# pca9544a_pcb.net
KiCad netlist of a schematic drawn in EAGLE
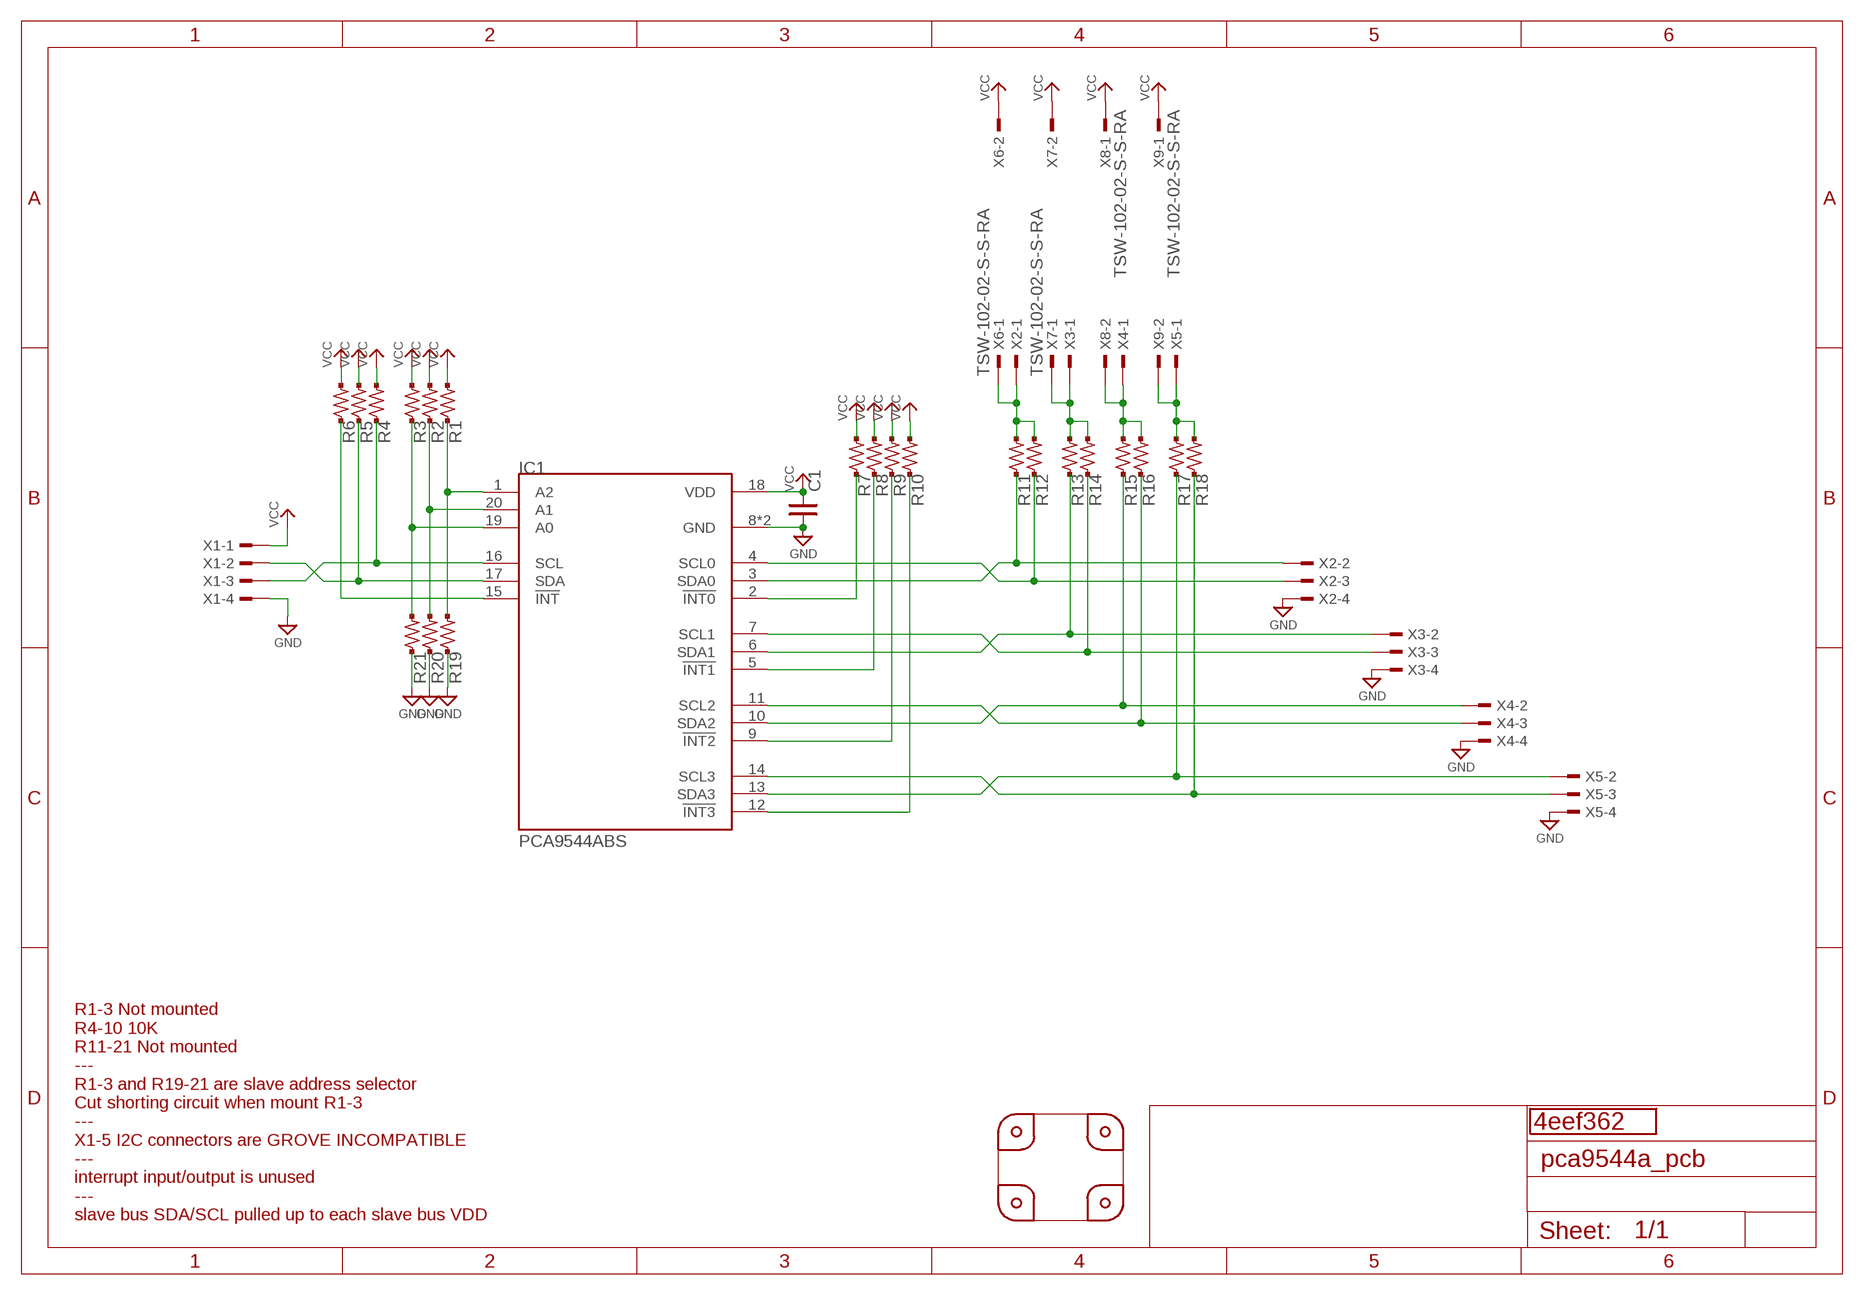
[diagram p0: schematic, sheet 1]

(export (version "E")
  (design (tool "Eeschema 10.0.6"))
  (components
    (comp (ref "C1")
      (value "C-SMD-0.1U-1608")
      (footprint "eagle-import:CR-1608")
      (libsource (lib "eagle-import") (part "C-SMD--16080.1U"))
    )
    (comp (ref "GIT1")
      (value "4eef362")
      (footprint "eagle-import:GIT-REVISION_1.2")
      (libsource (lib "eagle-import") (part "GIT-REVISION_1.2"))
    )
    (comp (ref "IC1")
      (value "PCA9544ABS")
      (footprint "eagle-import:QFN20-0.65P5.0X5.0")
      (libsource (lib "eagle-import") (part "PCA9544ABS"))
    )
    (comp (ref "P1")
      (value "PCB-CORNER")
      (footprint "eagle-import:PCB-CORNER")
      (libsource (lib "eagle-import") (part "PCB-CORNER"))
    )
    (comp (ref "P2")
      (value "PCB-CORNER")
      (footprint "eagle-import:PCB-CORNER")
      (libsource (lib "eagle-import") (part "PCB-CORNER"))
    )
    (comp (ref "P3")
      (value "PCB-CORNER")
      (footprint "eagle-import:PCB-CORNER")
      (libsource (lib "eagle-import") (part "PCB-CORNER"))
    )
    (comp (ref "P4")
      (value "PCB-CORNER")
      (footprint "eagle-import:PCB-CORNER")
      (libsource (lib "eagle-import") (part "PCB-CORNER"))
    )
    (comp (ref "R1")
      (value "R-US-10K-1608")
      (footprint "eagle-import:R-1608-PADPAD")
      (libsource (lib "eagle-import") (part "R-US--160810K"))
    )
    (comp (ref "R2")
      (value "R-US-10K-1608")
      (footprint "eagle-import:R-1608-PADPAD")
      (libsource (lib "eagle-import") (part "R-US--160810K"))
    )
    (comp (ref "R3")
      (value "R-US-10K-1608")
      (footprint "eagle-import:R-1608-PADPAD")
      (libsource (lib "eagle-import") (part "R-US--160810K"))
    )
    (comp (ref "R4")
      (value "R-US-10K-1608")
      (footprint "eagle-import:R-1608-PADPAD")
      (libsource (lib "eagle-import") (part "R-US--160810K"))
    )
    (comp (ref "R5")
      (value "R-US-10K-1608")
      (footprint "eagle-import:R-1608-PADPAD")
      (libsource (lib "eagle-import") (part "R-US--160810K"))
    )
    (comp (ref "R6")
      (value "R-US-10K-1608")
      (footprint "eagle-import:R-1608-PADPAD")
      (libsource (lib "eagle-import") (part "R-US--160810K"))
    )
    (comp (ref "R7")
      (value "R-US-10K-1608")
      (footprint "eagle-import:R-1608-PADPAD")
      (libsource (lib "eagle-import") (part "R-US--160810K"))
    )
    (comp (ref "R8")
      (value "R-US-10K-1608")
      (footprint "eagle-import:R-1608-PADPAD")
      (libsource (lib "eagle-import") (part "R-US--160810K"))
    )
    (comp (ref "R9")
      (value "R-US-10K-1608")
      (footprint "eagle-import:R-1608-PADPAD")
      (libsource (lib "eagle-import") (part "R-US--160810K"))
    )
    (comp (ref "R10")
      (value "R-US-10K-1608")
      (footprint "eagle-import:R-1608-PADPAD")
      (libsource (lib "eagle-import") (part "R-US--160810K"))
    )
    (comp (ref "R11")
      (value "R-US-10K-1608")
      (footprint "eagle-import:R-1608-PADPAD")
      (libsource (lib "eagle-import") (part "R-US--160810K"))
    )
    (comp (ref "R12")
      (value "R-US-10K-1608")
      (footprint "eagle-import:R-1608-PADPAD")
      (libsource (lib "eagle-import") (part "R-US--160810K"))
    )
    (comp (ref "R13")
      (value "R-US-10K-1608")
      (footprint "eagle-import:R-1608-PADPAD")
      (libsource (lib "eagle-import") (part "R-US--160810K"))
    )
    (comp (ref "R14")
      (value "R-US-10K-1608")
      (footprint "eagle-import:R-1608-PADPAD")
      (libsource (lib "eagle-import") (part "R-US--160810K"))
    )
    (comp (ref "R15")
      (value "R-US-10K-1608")
      (footprint "eagle-import:R-1608-PADPAD")
      (libsource (lib "eagle-import") (part "R-US--160810K"))
    )
    (comp (ref "R16")
      (value "R-US-10K-1608")
      (footprint "eagle-import:R-1608-PADPAD")
      (libsource (lib "eagle-import") (part "R-US--160810K"))
    )
    (comp (ref "R17")
      (value "R-US-10K-1608")
      (footprint "eagle-import:R-1608-PADPAD")
      (libsource (lib "eagle-import") (part "R-US--160810K"))
    )
    (comp (ref "R18")
      (value "R-US-10K-1608")
      (footprint "eagle-import:R-1608-PADPAD")
      (libsource (lib "eagle-import") (part "R-US--160810K"))
    )
    (comp (ref "R19")
      (value "R-US--1005SHORT")
      (footprint "eagle-import:R0402SHORT")
      (libsource (lib "eagle-import") (part "R-US--1005SHORT"))
    )
    (comp (ref "R20")
      (value "R-US--1005SHORT")
      (footprint "eagle-import:R0402SHORT")
      (libsource (lib "eagle-import") (part "R-US--1005SHORT"))
    )
    (comp (ref "R21")
      (value "R-US--1005SHORT")
      (footprint "eagle-import:R0402SHORT")
      (libsource (lib "eagle-import") (part "R-US--1005SHORT"))
    )
    (comp (ref "X1")
      (value "S4B-XH-A")
      (footprint "eagle-import:S4B-XH-A(LF)(SN)")
      (libsource (lib "eagle-import") (part "S4B-XH-A"))
    )
    (comp (ref "X2")
      (value "S4B-XH-A")
      (footprint "eagle-import:S4B-XH-A(LF)(SN)")
      (libsource (lib "eagle-import") (part "S4B-XH-A"))
    )
    (comp (ref "X3")
      (value "S4B-XH-A")
      (footprint "eagle-import:S4B-XH-A(LF)(SN)")
      (libsource (lib "eagle-import") (part "S4B-XH-A"))
    )
    (comp (ref "X4")
      (value "S4B-XH-A")
      (footprint "eagle-import:S4B-XH-A(LF)(SN)")
      (libsource (lib "eagle-import") (part "S4B-XH-A"))
    )
    (comp (ref "X5")
      (value "S4B-XH-A")
      (footprint "eagle-import:S4B-XH-A(LF)(SN)")
      (libsource (lib "eagle-import") (part "S4B-XH-A"))
    )
    (comp (ref "X6")
      (value "TSW-102-02-S-S-RA")
      (footprint "eagle-import:TSW-102-02-S-S-RA")
      (libsource (lib "eagle-import") (part "TSW-102-02-S-S-RA"))
    )
    (comp (ref "X7")
      (value "TSW-102-02-S-S-RA")
      (footprint "eagle-import:TSW-102-02-S-S-RA")
      (libsource (lib "eagle-import") (part "TSW-102-02-S-S-RA"))
    )
    (comp (ref "X8")
      (value "TSW-102-02-S-S-RA")
      (footprint "eagle-import:TSW-102-02-S-S-RA")
      (libsource (lib "eagle-import") (part "TSW-102-02-S-S-RA"))
    )
    (comp (ref "X9")
      (value "TSW-102-02-S-S-RA")
      (footprint "eagle-import:TSW-102-02-S-S-RA")
      (libsource (lib "eagle-import") (part "TSW-102-02-S-S-RA"))
    )
  )
  (nets
    (net (code "1") (name "GND") (class "Default")
      (node (ref "C1") (pin "2") (pinfunction "2_2") (pintype "passive"))
      (node (ref "IC1") (pin "8") (pinfunction "GND_8") (pintype "bidirectional"))
      (node (ref "IC1") (pin "EP") (pinfunction "GND_EP") (pintype "bidirectional"))
      (node (ref "R19") (pin "1") (pinfunction "1_1") (pintype "passive"))
      (node (ref "R19") (pin "2") (pinfunction "1_2") (pintype "passive"))
      (node (ref "R20") (pin "1") (pinfunction "1_1") (pintype "passive"))
      (node (ref "R20") (pin "2") (pinfunction "1_2") (pintype "passive"))
      (node (ref "R21") (pin "1") (pinfunction "1_1") (pintype "passive"))
      (node (ref "R21") (pin "2") (pinfunction "1_2") (pintype "passive"))
      (node (ref "X1") (pin "4") (pinfunction "1_4") (pintype "passive"))
      (node (ref "X2") (pin "4") (pinfunction "1_4") (pintype "passive"))
      (node (ref "X3") (pin "4") (pinfunction "1_4") (pintype "passive"))
      (node (ref "X4") (pin "4") (pinfunction "1_4") (pintype "passive"))
      (node (ref "X5") (pin "4") (pinfunction "1_4") (pintype "passive"))
    )
    (net (code "2") (name "Net-(IC1-A0)") (class "Default")
      (node (ref "IC1") (pin "19") (pinfunction "A0_19") (pintype "bidirectional"))
      (node (ref "R21") (pin "3") (pinfunction "2_3") (pintype "passive"))
      (node (ref "R3") (pin "1") (pinfunction "1_1") (pintype "passive"))
    )
    (net (code "3") (name "Net-(IC1-A1)") (class "Default")
      (node (ref "IC1") (pin "20") (pinfunction "A1_20") (pintype "bidirectional"))
      (node (ref "R2") (pin "1") (pinfunction "1_1") (pintype "passive"))
      (node (ref "R20") (pin "3") (pinfunction "2_3") (pintype "passive"))
    )
    (net (code "4") (name "Net-(IC1-A2)") (class "Default")
      (node (ref "IC1") (pin "1") (pinfunction "A2_1") (pintype "bidirectional"))
      (node (ref "R1") (pin "1") (pinfunction "1_1") (pintype "passive"))
      (node (ref "R19") (pin "3") (pinfunction "2_3") (pintype "passive"))
    )
    (net (code "5") (name "Net-(IC1-SCL)") (class "Default")
      (node (ref "IC1") (pin "16") (pinfunction "SCL_16") (pintype "bidirectional"))
      (node (ref "R4") (pin "1") (pinfunction "1_1") (pintype "passive"))
      (node (ref "X1") (pin "3") (pinfunction "1_3") (pintype "passive"))
    )
    (net (code "6") (name "Net-(IC1-SCL0)") (class "Default")
      (node (ref "IC1") (pin "4") (pinfunction "SCL0_4") (pintype "bidirectional"))
      (node (ref "R12") (pin "1") (pinfunction "1_1") (pintype "passive"))
      (node (ref "X2") (pin "3") (pinfunction "1_3") (pintype "passive"))
    )
    (net (code "7") (name "Net-(IC1-SCL1)") (class "Default")
      (node (ref "IC1") (pin "7") (pinfunction "SCL1_7") (pintype "bidirectional"))
      (node (ref "R14") (pin "1") (pinfunction "1_1") (pintype "passive"))
      (node (ref "X3") (pin "3") (pinfunction "1_3") (pintype "passive"))
    )
    (net (code "8") (name "Net-(IC1-SCL2)") (class "Default")
      (node (ref "IC1") (pin "11") (pinfunction "SCL2_11") (pintype "bidirectional"))
      (node (ref "R16") (pin "1") (pinfunction "1_1") (pintype "passive"))
      (node (ref "X4") (pin "3") (pinfunction "1_3") (pintype "passive"))
    )
    (net (code "9") (name "Net-(IC1-SCL3)") (class "Default")
      (node (ref "IC1") (pin "14") (pinfunction "SCL3_14") (pintype "bidirectional"))
      (node (ref "R18") (pin "1") (pinfunction "1_1") (pintype "passive"))
      (node (ref "X5") (pin "3") (pinfunction "1_3") (pintype "passive"))
    )
    (net (code "10") (name "Net-(IC1-SDA)") (class "Default")
      (node (ref "IC1") (pin "17") (pinfunction "SDA_17") (pintype "bidirectional"))
      (node (ref "R5") (pin "1") (pinfunction "1_1") (pintype "passive"))
      (node (ref "X1") (pin "2") (pinfunction "1_2") (pintype "passive"))
    )
    (net (code "11") (name "Net-(IC1-SDA0)") (class "Default")
      (node (ref "IC1") (pin "3") (pinfunction "SDA0_3") (pintype "bidirectional"))
      (node (ref "R11") (pin "1") (pinfunction "1_1") (pintype "passive"))
      (node (ref "X2") (pin "2") (pinfunction "1_2") (pintype "passive"))
    )
    (net (code "12") (name "Net-(IC1-SDA1)") (class "Default")
      (node (ref "IC1") (pin "6") (pinfunction "SDA1_6") (pintype "bidirectional"))
      (node (ref "R13") (pin "1") (pinfunction "1_1") (pintype "passive"))
      (node (ref "X3") (pin "2") (pinfunction "1_2") (pintype "passive"))
    )
    (net (code "13") (name "Net-(IC1-SDA2)") (class "Default")
      (node (ref "IC1") (pin "10") (pinfunction "SDA2_10") (pintype "bidirectional"))
      (node (ref "R15") (pin "1") (pinfunction "1_1") (pintype "passive"))
      (node (ref "X4") (pin "2") (pinfunction "1_2") (pintype "passive"))
    )
    (net (code "14") (name "Net-(IC1-SDA3)") (class "Default")
      (node (ref "IC1") (pin "13") (pinfunction "SDA3_13") (pintype "bidirectional"))
      (node (ref "R17") (pin "1") (pinfunction "1_1") (pintype "passive"))
      (node (ref "X5") (pin "2") (pinfunction "1_2") (pintype "passive"))
    )
    (net (code "15") (name "Net-(IC1-~{INT0})") (class "Default")
      (node (ref "IC1") (pin "2") (pinfunction "~{INT0}_2") (pintype "bidirectional"))
      (node (ref "R7") (pin "1") (pinfunction "1_1") (pintype "passive"))
    )
    (net (code "16") (name "Net-(IC1-~{INT1})") (class "Default")
      (node (ref "IC1") (pin "5") (pinfunction "~{INT1}_5") (pintype "bidirectional"))
      (node (ref "R8") (pin "1") (pinfunction "1_1") (pintype "passive"))
    )
    (net (code "17") (name "Net-(IC1-~{INT2})") (class "Default")
      (node (ref "IC1") (pin "9") (pinfunction "~{INT2}_9") (pintype "bidirectional"))
      (node (ref "R9") (pin "1") (pinfunction "1_1") (pintype "passive"))
    )
    (net (code "18") (name "Net-(IC1-~{INT3})") (class "Default")
      (node (ref "IC1") (pin "12") (pinfunction "~{INT3}_12") (pintype "bidirectional"))
      (node (ref "R10") (pin "1") (pinfunction "1_1") (pintype "passive"))
    )
    (net (code "19") (name "Net-(IC1-~{INT})") (class "Default")
      (node (ref "IC1") (pin "15") (pinfunction "~{INT}_15") (pintype "bidirectional"))
      (node (ref "R6") (pin "1") (pinfunction "1_1") (pintype "passive"))
    )
    (net (code "20") (name "Net-(R11-Pad2)") (class "Default")
      (node (ref "R11") (pin "2") (pinfunction "2_2") (pintype "passive"))
      (node (ref "R12") (pin "2") (pinfunction "2_2") (pintype "passive"))
      (node (ref "X2") (pin "1") (pinfunction "1_1") (pintype "passive"))
      (node (ref "X6") (pin "1") (pinfunction "1_1") (pintype "passive"))
    )
    (net (code "21") (name "Net-(R13-Pad2)") (class "Default")
      (node (ref "R13") (pin "2") (pinfunction "2_2") (pintype "passive"))
      (node (ref "R14") (pin "2") (pinfunction "2_2") (pintype "passive"))
      (node (ref "X3") (pin "1") (pinfunction "1_1") (pintype "passive"))
      (node (ref "X7") (pin "1") (pinfunction "1_1") (pintype "passive"))
    )
    (net (code "22") (name "Net-(X8B-1)") (class "Default")
      (node (ref "R15") (pin "2") (pinfunction "2_2") (pintype "passive"))
      (node (ref "R16") (pin "2") (pinfunction "2_2") (pintype "passive"))
      (node (ref "X4") (pin "1") (pinfunction "1_1") (pintype "passive"))
      (node (ref "X8") (pin "2") (pinfunction "1_2") (pintype "passive"))
    )
    (net (code "23") (name "Net-(X9B-1)") (class "Default")
      (node (ref "R17") (pin "2") (pinfunction "2_2") (pintype "passive"))
      (node (ref "R18") (pin "2") (pinfunction "2_2") (pintype "passive"))
      (node (ref "X5") (pin "1") (pinfunction "1_1") (pintype "passive"))
      (node (ref "X9") (pin "2") (pinfunction "1_2") (pintype "passive"))
    )
    (net (code "24") (name "VCC") (class "Default")
      (node (ref "C1") (pin "1") (pinfunction "1_1") (pintype "passive"))
      (node (ref "IC1") (pin "18") (pinfunction "VDD_18") (pintype "bidirectional"))
      (node (ref "R1") (pin "2") (pinfunction "2_2") (pintype "passive"))
      (node (ref "R10") (pin "2") (pinfunction "2_2") (pintype "passive"))
      (node (ref "R2") (pin "2") (pinfunction "2_2") (pintype "passive"))
      (node (ref "R3") (pin "2") (pinfunction "2_2") (pintype "passive"))
      (node (ref "R4") (pin "2") (pinfunction "2_2") (pintype "passive"))
      (node (ref "R5") (pin "2") (pinfunction "2_2") (pintype "passive"))
      (node (ref "R6") (pin "2") (pinfunction "2_2") (pintype "passive"))
      (node (ref "R7") (pin "2") (pinfunction "2_2") (pintype "passive"))
      (node (ref "R8") (pin "2") (pinfunction "2_2") (pintype "passive"))
      (node (ref "R9") (pin "2") (pinfunction "2_2") (pintype "passive"))
      (node (ref "X1") (pin "1") (pinfunction "1_1") (pintype "passive"))
      (node (ref "X6") (pin "2") (pinfunction "1_2") (pintype "passive"))
      (node (ref "X7") (pin "2") (pinfunction "1_2") (pintype "passive"))
      (node (ref "X8") (pin "1") (pinfunction "1_1") (pintype "passive"))
      (node (ref "X9") (pin "1") (pinfunction "1_1") (pintype "passive"))
    )
  )
)
